# ADC_Connections.net
KiCad netlist of a schematic drawn in Altium Designer
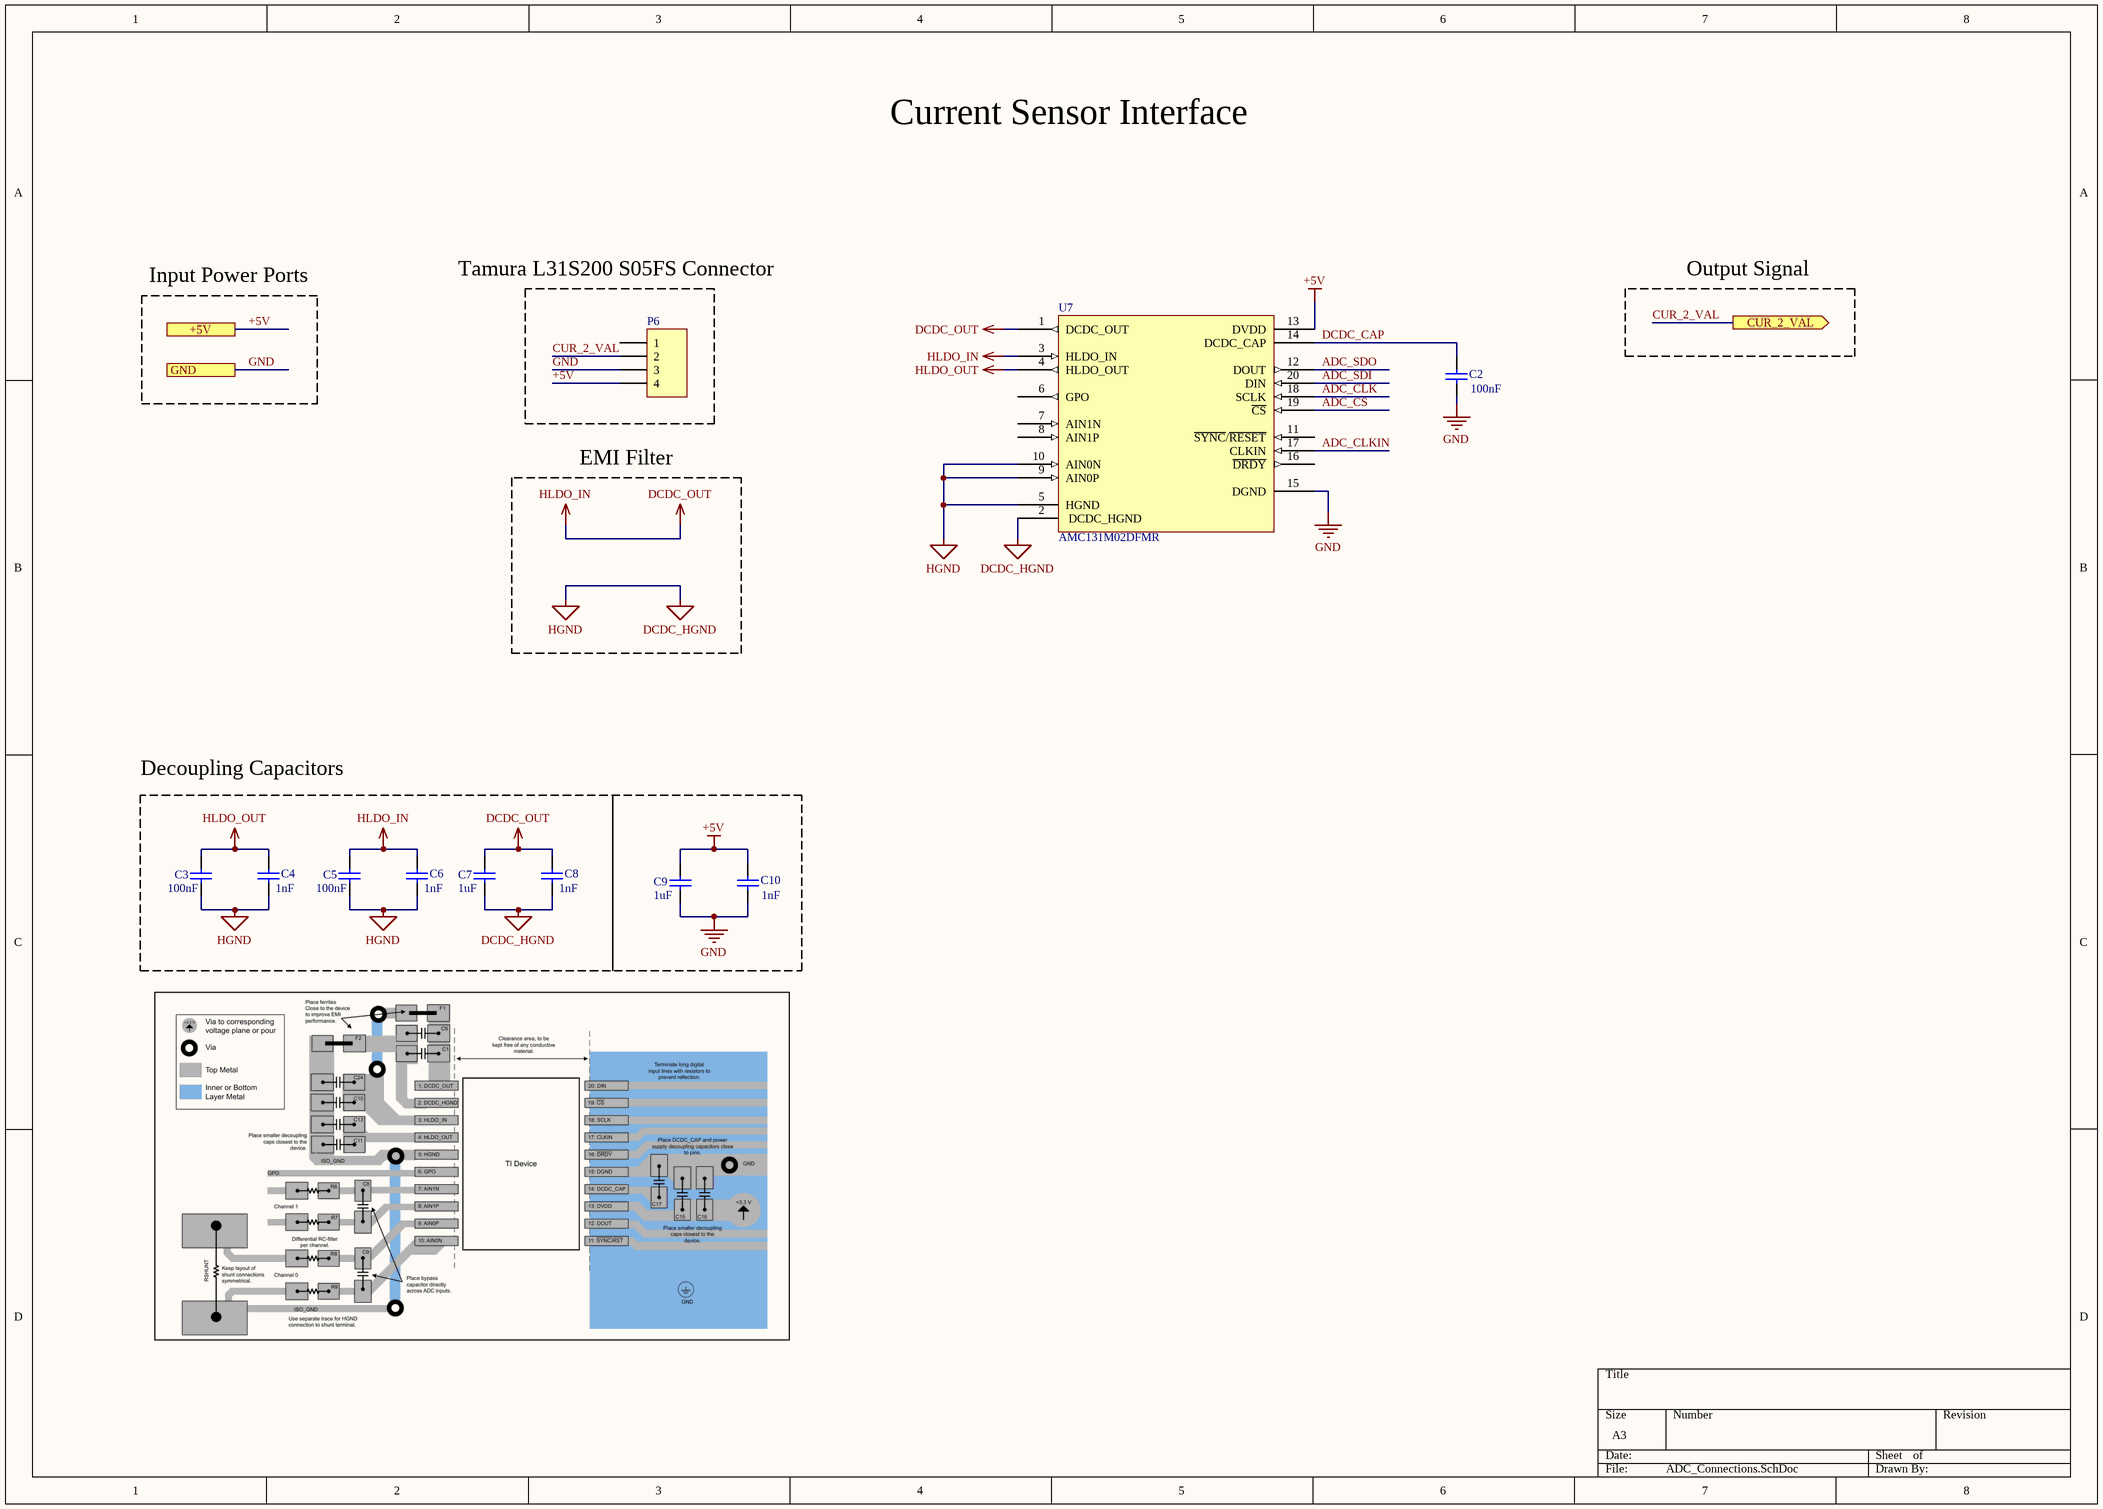
[diagram p0: ADC_Connections.SchDoc]

(export (version "E")
  (design (tool "Eeschema 10.0.6"))
  (components
    (comp (ref "C2")
      (value "100nF")
      (footprint "RAD-0.3")
      (description "Capacitor")
      (fields (field (name "Comment") "Cap") (field (name "PUBLISHER") "Altium Limited"))
      (libsource (lib "Miscellaneous Devices") (part "Cap"))
    )
    (comp (ref "C3")
      (value "100nF")
      (footprint "RAD-0.3")
      (description "Capacitor")
      (fields (field (name "Comment") "Cap") (field (name "PUBLISHER") "Altium Limited"))
      (libsource (lib "Miscellaneous Devices") (part "Cap"))
    )
    (comp (ref "C4")
      (value "1nF")
      (footprint "RAD-0.3")
      (description "Capacitor")
      (fields (field (name "Comment") "Cap") (field (name "PUBLISHER") "Altium Limited"))
      (libsource (lib "Miscellaneous Devices") (part "Cap"))
    )
    (comp (ref "C5")
      (value "100nF")
      (footprint "RAD-0.3")
      (description "Capacitor")
      (fields (field (name "Comment") "Cap") (field (name "PUBLISHER") "Altium Limited"))
      (libsource (lib "Miscellaneous Devices") (part "Cap"))
    )
    (comp (ref "C6")
      (value "1nF")
      (footprint "RAD-0.3")
      (description "Capacitor")
      (fields (field (name "Comment") "Cap") (field (name "PUBLISHER") "Altium Limited"))
      (libsource (lib "Miscellaneous Devices") (part "Cap"))
    )
    (comp (ref "C7")
      (value "1uF")
      (footprint "RAD-0.3")
      (description "Capacitor")
      (fields (field (name "Comment") "Cap") (field (name "PUBLISHER") "Altium Limited"))
      (libsource (lib "Miscellaneous Devices") (part "Cap"))
    )
    (comp (ref "C8")
      (value "1nF")
      (footprint "RAD-0.3")
      (description "Capacitor")
      (fields (field (name "Comment") "Cap") (field (name "PUBLISHER") "Altium Limited"))
      (libsource (lib "Miscellaneous Devices") (part "Cap"))
    )
    (comp (ref "C9")
      (value "1uF")
      (footprint "RAD-0.3")
      (description "Capacitor")
      (fields (field (name "Comment") "Cap") (field (name "PUBLISHER") "Altium Limited"))
      (libsource (lib "Miscellaneous Devices") (part "Cap"))
    )
    (comp (ref "C10")
      (value "1nF")
      (footprint "RAD-0.3")
      (description "Capacitor")
      (fields (field (name "Comment") "Cap") (field (name "PUBLISHER") "Altium Limited"))
      (libsource (lib "Miscellaneous Devices") (part "Cap"))
    )
    (comp (ref "P6")
      (value "Header 4")
      (footprint "HDR1X4")
      (description "Header, 4-Pin")
      (fields (field (name "PUBLISHER") "Altium Limited"))
      (libsource (lib "TD") (part "Header 4H"))
    )
    (comp (ref "U7")
      (value "AMC131M02DFMR")
      (footprint "SOIC20")
      (libsource (lib "SiProFaSi") (part "AMC131M02DFMR"))
    )
  )
  (nets
    (net (code "1") (name "+5V") (class "Default")
      (node (ref "C10") (pin "2") (pinfunction "2_2") (pintype "passive"))
      (node (ref "C9") (pin "2") (pinfunction "2_2") (pintype "passive"))
      (node (ref "P6") (pin "4") (pinfunction "4_4") (pintype "passive"))
      (node (ref "U7") (pin "13") (pinfunction "DVDD_13") (pintype "power_in"))
    )
    (net (code "2") (name "/ADC_CLK") (class "Default")
      (node (ref "U7") (pin "18") (pinfunction "SCLK_18") (pintype "input"))
    )
    (net (code "3") (name "/ADC_CLKIN") (class "Default")
      (node (ref "U7") (pin "17") (pinfunction "CLKIN_17") (pintype "input"))
    )
    (net (code "4") (name "/ADC_CS") (class "Default")
      (node (ref "U7") (pin "19") (pinfunction "~{CS}_19") (pintype "input"))
    )
    (net (code "5") (name "/ADC_SDI") (class "Default")
      (node (ref "U7") (pin "20") (pinfunction "DIN_20") (pintype "input"))
    )
    (net (code "6") (name "/ADC_SDO") (class "Default")
      (node (ref "U7") (pin "12") (pinfunction "DOUT_12") (pintype "output"))
    )
    (net (code "7") (name "/CUR_2_VAL") (class "Default")
      (node (ref "P6") (pin "2") (pinfunction "2_2") (pintype "passive"))
    )
    (net (code "8") (name "/DCDC_CAP") (class "Default")
      (node (ref "C2") (pin "2") (pinfunction "2_2") (pintype "passive"))
      (node (ref "U7") (pin "14") (pinfunction "DCDC_CAP_14") (pintype "power_in"))
    )
    (net (code "9") (name "DCDC_HGND") (class "Default")
      (node (ref "C3") (pin "1") (pinfunction "1_1") (pintype "passive"))
      (node (ref "C4") (pin "1") (pinfunction "1_1") (pintype "passive"))
      (node (ref "C5") (pin "1") (pinfunction "1_1") (pintype "passive"))
      (node (ref "C6") (pin "1") (pinfunction "1_1") (pintype "passive"))
      (node (ref "C7") (pin "1") (pinfunction "1_1") (pintype "passive"))
      (node (ref "C8") (pin "1") (pinfunction "1_1") (pintype "passive"))
      (node (ref "U7") (pin "10") (pinfunction "AIN0N_10") (pintype "input"))
      (node (ref "U7") (pin "2") (pinfunction "_DCDC_HGND_2") (pintype "passive"))
      (node (ref "U7") (pin "5") (pinfunction "HGND_5") (pintype "passive"))
      (node (ref "U7") (pin "9") (pinfunction "AIN0P_9") (pintype "input"))
    )
    (net (code "10") (name "DCDC_OUT") (class "Default")
      (node (ref "C5") (pin "2") (pinfunction "2_2") (pintype "passive"))
      (node (ref "C6") (pin "2") (pinfunction "2_2") (pintype "passive"))
      (node (ref "C7") (pin "2") (pinfunction "2_2") (pintype "passive"))
      (node (ref "C8") (pin "2") (pinfunction "2_2") (pintype "passive"))
      (node (ref "U7") (pin "1") (pinfunction "DCDC_OUT_1") (pintype "output"))
      (node (ref "U7") (pin "3") (pinfunction "HLDO_IN_3") (pintype "input"))
    )
    (net (code "11") (name "GND") (class "Default")
      (node (ref "C10") (pin "1") (pinfunction "1_1") (pintype "passive"))
      (node (ref "C2") (pin "1") (pinfunction "1_1") (pintype "passive"))
      (node (ref "C9") (pin "1") (pinfunction "1_1") (pintype "passive"))
      (node (ref "P6") (pin "3") (pinfunction "3_3") (pintype "passive"))
      (node (ref "U7") (pin "15") (pinfunction "DGND_15") (pintype "passive"))
    )
    (net (code "12") (name "HLDO_OUT") (class "Default")
      (node (ref "C3") (pin "2") (pinfunction "2_2") (pintype "passive"))
      (node (ref "C4") (pin "2") (pinfunction "2_2") (pintype "passive"))
      (node (ref "U7") (pin "4") (pinfunction "HLDO_OUT_4") (pintype "output"))
    )
    (net (code "13") (name "unconnected-(P6-Pad1)") (class "Default")
      (node (ref "P6") (pin "1") (pinfunction "1_1") (pintype "passive"))
    )
    (net (code "14") (name "unconnected-(U7-AIN1N-Pad7)") (class "Default")
      (node (ref "U7") (pin "7") (pinfunction "AIN1N_7") (pintype "input"))
    )
    (net (code "15") (name "unconnected-(U7-AIN1P-Pad8)") (class "Default")
      (node (ref "U7") (pin "8") (pinfunction "AIN1P_8") (pintype "input"))
    )
    (net (code "16") (name "unconnected-(U7-GPO-Pad6)") (class "Default")
      (node (ref "U7") (pin "6") (pinfunction "GPO_6") (pintype "output"))
    )
    (net (code "17") (name "unconnected-(U7-~{DRDY}-Pad16)") (class "Default")
      (node (ref "U7") (pin "16") (pinfunction "~{DRDY}_16") (pintype "output"))
    )
    (net (code "18") (name "unconnected-(U7-~{SYNC}{slash}~{RESET}-Pad11)") (class "Default")
      (node (ref "U7") (pin "11") (pinfunction "~{SYNC}/~{RESET}_11") (pintype "input"))
    )
  )
)
